# ws2812_wyswietlacz.net
KiCad netlist of a schematic drawn in EAGLE
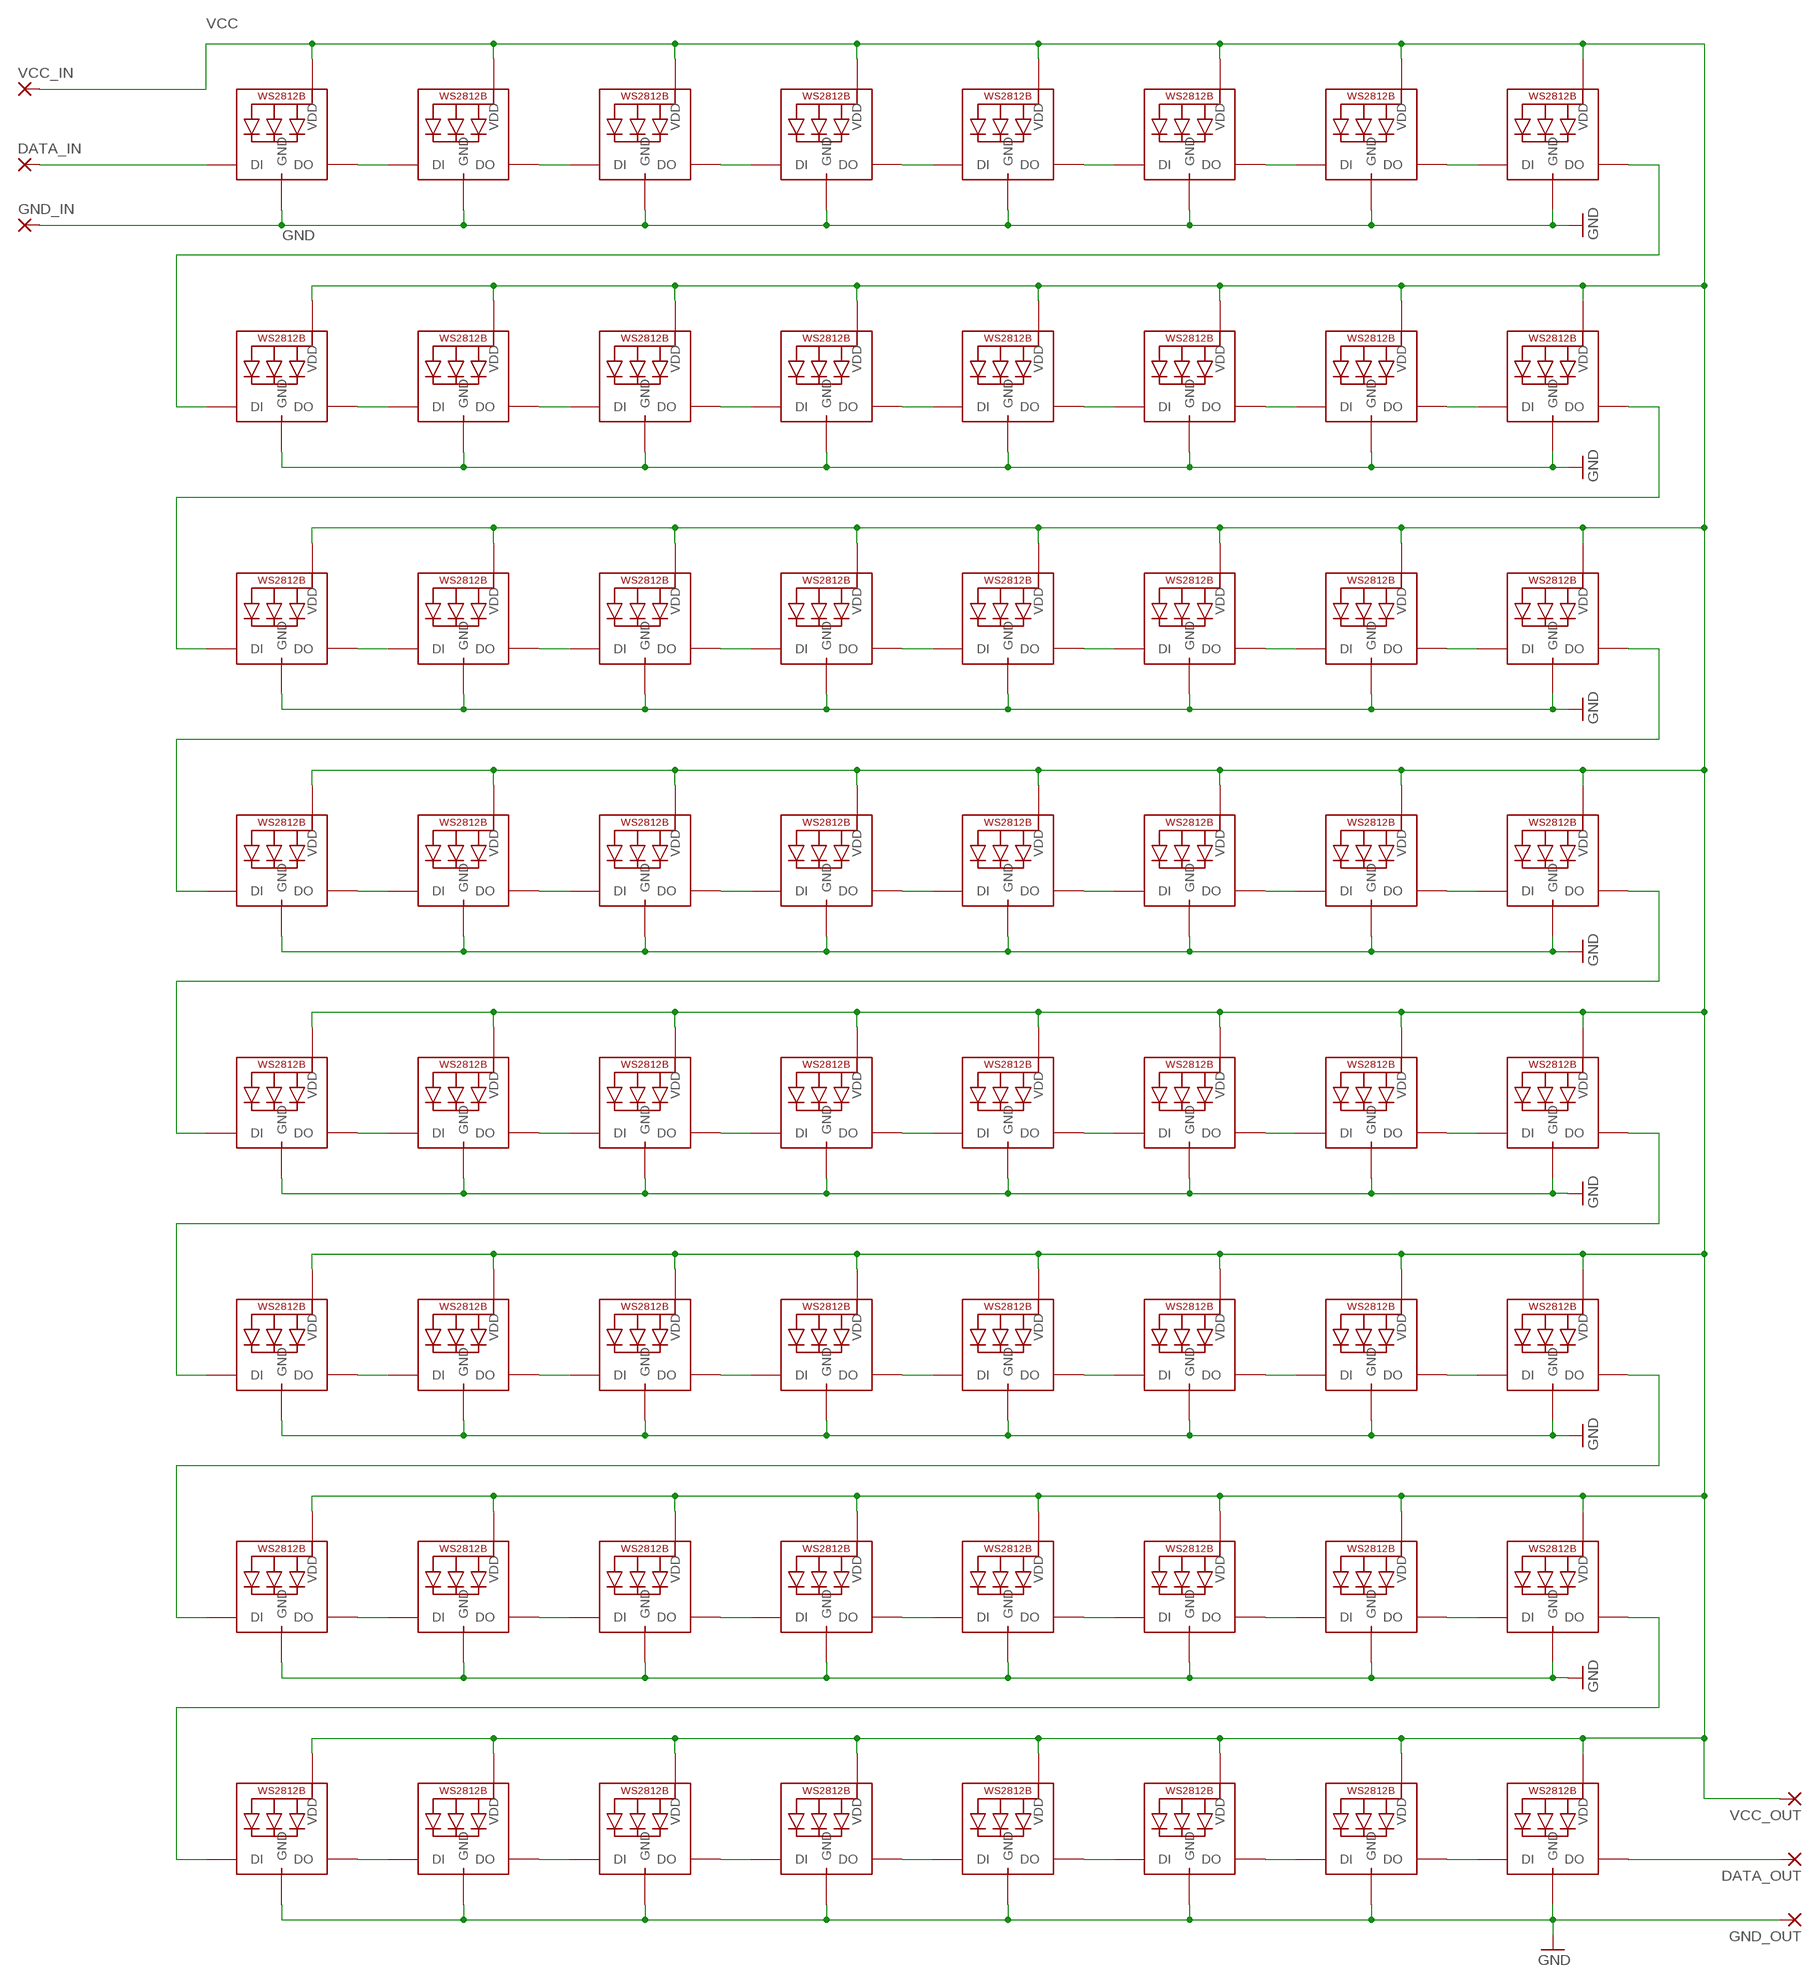
[diagram p0: schematic, sheet 1]

(export (version "E")
  (design (tool "Eeschema 10.0.6"))
  (components
    (comp (ref "DATA_IN")
      (value "2,54/1,0")
      (footprint "eagle-import:2,54_1,0")
      (libsource (lib "eagle-import") (part "2,54/1,0"))
    )
    (comp (ref "DATA_OUT")
      (value "2,54/1,0")
      (footprint "eagle-import:2,54_1,0")
      (libsource (lib "eagle-import") (part "2,54/1,0"))
    )
    (comp (ref "GND_IN")
      (value "2,54/1,0")
      (footprint "eagle-import:2,54_1,0")
      (libsource (lib "eagle-import") (part "2,54/1,0"))
    )
    (comp (ref "GND_OUT")
      (value "2,54/1,0")
      (footprint "eagle-import:2,54_1,0")
      (libsource (lib "eagle-import") (part "2,54/1,0"))
    )
    (comp (ref "LED1")
      (value "WS2812B_5050N")
      (footprint "eagle-import:WS2812B-NARROW")
      (libsource (lib "eagle-import") (part "WS2812B_5050N"))
    )
    (comp (ref "LED2")
      (value "WS2812B_5050N")
      (footprint "eagle-import:WS2812B-NARROW")
      (libsource (lib "eagle-import") (part "WS2812B_5050N"))
    )
    (comp (ref "LED3")
      (value "WS2812B_5050N")
      (footprint "eagle-import:WS2812B-NARROW")
      (libsource (lib "eagle-import") (part "WS2812B_5050N"))
    )
    (comp (ref "LED4")
      (value "WS2812B_5050N")
      (footprint "eagle-import:WS2812B-NARROW")
      (libsource (lib "eagle-import") (part "WS2812B_5050N"))
    )
    (comp (ref "LED5")
      (value "WS2812B_5050N")
      (footprint "eagle-import:WS2812B-NARROW")
      (libsource (lib "eagle-import") (part "WS2812B_5050N"))
    )
    (comp (ref "LED6")
      (value "WS2812B_5050N")
      (footprint "eagle-import:WS2812B-NARROW")
      (libsource (lib "eagle-import") (part "WS2812B_5050N"))
    )
    (comp (ref "LED7")
      (value "WS2812B_5050N")
      (footprint "eagle-import:WS2812B-NARROW")
      (libsource (lib "eagle-import") (part "WS2812B_5050N"))
    )
    (comp (ref "LED8")
      (value "WS2812B_5050N")
      (footprint "eagle-import:WS2812B-NARROW")
      (libsource (lib "eagle-import") (part "WS2812B_5050N"))
    )
    (comp (ref "LED9")
      (value "WS2812B_5050N")
      (footprint "eagle-import:WS2812B-NARROW")
      (libsource (lib "eagle-import") (part "WS2812B_5050N"))
    )
    (comp (ref "LED10")
      (value "WS2812B_5050N")
      (footprint "eagle-import:WS2812B-NARROW")
      (libsource (lib "eagle-import") (part "WS2812B_5050N"))
    )
    (comp (ref "LED11")
      (value "WS2812B_5050N")
      (footprint "eagle-import:WS2812B-NARROW")
      (libsource (lib "eagle-import") (part "WS2812B_5050N"))
    )
    (comp (ref "LED12")
      (value "WS2812B_5050N")
      (footprint "eagle-import:WS2812B-NARROW")
      (libsource (lib "eagle-import") (part "WS2812B_5050N"))
    )
    (comp (ref "LED13")
      (value "WS2812B_5050N")
      (footprint "eagle-import:WS2812B-NARROW")
      (libsource (lib "eagle-import") (part "WS2812B_5050N"))
    )
    (comp (ref "LED14")
      (value "WS2812B_5050N")
      (footprint "eagle-import:WS2812B-NARROW")
      (libsource (lib "eagle-import") (part "WS2812B_5050N"))
    )
    (comp (ref "LED15")
      (value "WS2812B_5050N")
      (footprint "eagle-import:WS2812B-NARROW")
      (libsource (lib "eagle-import") (part "WS2812B_5050N"))
    )
    (comp (ref "LED16")
      (value "WS2812B_5050N")
      (footprint "eagle-import:WS2812B-NARROW")
      (libsource (lib "eagle-import") (part "WS2812B_5050N"))
    )
    (comp (ref "LED17")
      (value "WS2812B_5050N")
      (footprint "eagle-import:WS2812B-NARROW")
      (libsource (lib "eagle-import") (part "WS2812B_5050N"))
    )
    (comp (ref "LED18")
      (value "WS2812B_5050N")
      (footprint "eagle-import:WS2812B-NARROW")
      (libsource (lib "eagle-import") (part "WS2812B_5050N"))
    )
    (comp (ref "LED19")
      (value "WS2812B_5050N")
      (footprint "eagle-import:WS2812B-NARROW")
      (libsource (lib "eagle-import") (part "WS2812B_5050N"))
    )
    (comp (ref "LED20")
      (value "WS2812B_5050N")
      (footprint "eagle-import:WS2812B-NARROW")
      (libsource (lib "eagle-import") (part "WS2812B_5050N"))
    )
    (comp (ref "LED21")
      (value "WS2812B_5050N")
      (footprint "eagle-import:WS2812B-NARROW")
      (libsource (lib "eagle-import") (part "WS2812B_5050N"))
    )
    (comp (ref "LED22")
      (value "WS2812B_5050N")
      (footprint "eagle-import:WS2812B-NARROW")
      (libsource (lib "eagle-import") (part "WS2812B_5050N"))
    )
    (comp (ref "LED23")
      (value "WS2812B_5050N")
      (footprint "eagle-import:WS2812B-NARROW")
      (libsource (lib "eagle-import") (part "WS2812B_5050N"))
    )
    (comp (ref "LED24")
      (value "WS2812B_5050N")
      (footprint "eagle-import:WS2812B-NARROW")
      (libsource (lib "eagle-import") (part "WS2812B_5050N"))
    )
    (comp (ref "LED25")
      (value "WS2812B_5050N")
      (footprint "eagle-import:WS2812B-NARROW")
      (libsource (lib "eagle-import") (part "WS2812B_5050N"))
    )
    (comp (ref "LED26")
      (value "WS2812B_5050N")
      (footprint "eagle-import:WS2812B-NARROW")
      (libsource (lib "eagle-import") (part "WS2812B_5050N"))
    )
    (comp (ref "LED27")
      (value "WS2812B_5050N")
      (footprint "eagle-import:WS2812B-NARROW")
      (libsource (lib "eagle-import") (part "WS2812B_5050N"))
    )
    (comp (ref "LED28")
      (value "WS2812B_5050N")
      (footprint "eagle-import:WS2812B-NARROW")
      (libsource (lib "eagle-import") (part "WS2812B_5050N"))
    )
    (comp (ref "LED29")
      (value "WS2812B_5050N")
      (footprint "eagle-import:WS2812B-NARROW")
      (libsource (lib "eagle-import") (part "WS2812B_5050N"))
    )
    (comp (ref "LED30")
      (value "WS2812B_5050N")
      (footprint "eagle-import:WS2812B-NARROW")
      (libsource (lib "eagle-import") (part "WS2812B_5050N"))
    )
    (comp (ref "LED31")
      (value "WS2812B_5050N")
      (footprint "eagle-import:WS2812B-NARROW")
      (libsource (lib "eagle-import") (part "WS2812B_5050N"))
    )
    (comp (ref "LED32")
      (value "WS2812B_5050N")
      (footprint "eagle-import:WS2812B-NARROW")
      (libsource (lib "eagle-import") (part "WS2812B_5050N"))
    )
    (comp (ref "LED33")
      (value "WS2812B_5050N")
      (footprint "eagle-import:WS2812B-NARROW")
      (libsource (lib "eagle-import") (part "WS2812B_5050N"))
    )
    (comp (ref "LED34")
      (value "WS2812B_5050N")
      (footprint "eagle-import:WS2812B-NARROW")
      (libsource (lib "eagle-import") (part "WS2812B_5050N"))
    )
    (comp (ref "LED35")
      (value "WS2812B_5050N")
      (footprint "eagle-import:WS2812B-NARROW")
      (libsource (lib "eagle-import") (part "WS2812B_5050N"))
    )
    (comp (ref "LED36")
      (value "WS2812B_5050N")
      (footprint "eagle-import:WS2812B-NARROW")
      (libsource (lib "eagle-import") (part "WS2812B_5050N"))
    )
    (comp (ref "LED37")
      (value "WS2812B_5050N")
      (footprint "eagle-import:WS2812B-NARROW")
      (libsource (lib "eagle-import") (part "WS2812B_5050N"))
    )
    (comp (ref "LED38")
      (value "WS2812B_5050N")
      (footprint "eagle-import:WS2812B-NARROW")
      (libsource (lib "eagle-import") (part "WS2812B_5050N"))
    )
    (comp (ref "LED39")
      (value "WS2812B_5050N")
      (footprint "eagle-import:WS2812B-NARROW")
      (libsource (lib "eagle-import") (part "WS2812B_5050N"))
    )
    (comp (ref "LED40")
      (value "WS2812B_5050N")
      (footprint "eagle-import:WS2812B-NARROW")
      (libsource (lib "eagle-import") (part "WS2812B_5050N"))
    )
    (comp (ref "LED41")
      (value "WS2812B_5050N")
      (footprint "eagle-import:WS2812B-NARROW")
      (libsource (lib "eagle-import") (part "WS2812B_5050N"))
    )
    (comp (ref "LED42")
      (value "WS2812B_5050N")
      (footprint "eagle-import:WS2812B-NARROW")
      (libsource (lib "eagle-import") (part "WS2812B_5050N"))
    )
    (comp (ref "LED43")
      (value "WS2812B_5050N")
      (footprint "eagle-import:WS2812B-NARROW")
      (libsource (lib "eagle-import") (part "WS2812B_5050N"))
    )
    (comp (ref "LED44")
      (value "WS2812B_5050N")
      (footprint "eagle-import:WS2812B-NARROW")
      (libsource (lib "eagle-import") (part "WS2812B_5050N"))
    )
    (comp (ref "LED45")
      (value "WS2812B_5050N")
      (footprint "eagle-import:WS2812B-NARROW")
      (libsource (lib "eagle-import") (part "WS2812B_5050N"))
    )
    (comp (ref "LED46")
      (value "WS2812B_5050N")
      (footprint "eagle-import:WS2812B-NARROW")
      (libsource (lib "eagle-import") (part "WS2812B_5050N"))
    )
    (comp (ref "LED47")
      (value "WS2812B_5050N")
      (footprint "eagle-import:WS2812B-NARROW")
      (libsource (lib "eagle-import") (part "WS2812B_5050N"))
    )
    (comp (ref "LED48")
      (value "WS2812B_5050N")
      (footprint "eagle-import:WS2812B-NARROW")
      (libsource (lib "eagle-import") (part "WS2812B_5050N"))
    )
    (comp (ref "LED49")
      (value "WS2812B_5050N")
      (footprint "eagle-import:WS2812B-NARROW")
      (libsource (lib "eagle-import") (part "WS2812B_5050N"))
    )
    (comp (ref "LED50")
      (value "WS2812B_5050N")
      (footprint "eagle-import:WS2812B-NARROW")
      (libsource (lib "eagle-import") (part "WS2812B_5050N"))
    )
    (comp (ref "LED51")
      (value "WS2812B_5050N")
      (footprint "eagle-import:WS2812B-NARROW")
      (libsource (lib "eagle-import") (part "WS2812B_5050N"))
    )
    (comp (ref "LED52")
      (value "WS2812B_5050N")
      (footprint "eagle-import:WS2812B-NARROW")
      (libsource (lib "eagle-import") (part "WS2812B_5050N"))
    )
    (comp (ref "LED53")
      (value "WS2812B_5050N")
      (footprint "eagle-import:WS2812B-NARROW")
      (libsource (lib "eagle-import") (part "WS2812B_5050N"))
    )
    (comp (ref "LED54")
      (value "WS2812B_5050N")
      (footprint "eagle-import:WS2812B-NARROW")
      (libsource (lib "eagle-import") (part "WS2812B_5050N"))
    )
    (comp (ref "LED55")
      (value "WS2812B_5050N")
      (footprint "eagle-import:WS2812B-NARROW")
      (libsource (lib "eagle-import") (part "WS2812B_5050N"))
    )
    (comp (ref "LED56")
      (value "WS2812B_5050N")
      (footprint "eagle-import:WS2812B-NARROW")
      (libsource (lib "eagle-import") (part "WS2812B_5050N"))
    )
    (comp (ref "LED57")
      (value "WS2812B_5050N")
      (footprint "eagle-import:WS2812B-NARROW")
      (libsource (lib "eagle-import") (part "WS2812B_5050N"))
    )
    (comp (ref "LED58")
      (value "WS2812B_5050N")
      (footprint "eagle-import:WS2812B-NARROW")
      (libsource (lib "eagle-import") (part "WS2812B_5050N"))
    )
    (comp (ref "LED59")
      (value "WS2812B_5050N")
      (footprint "eagle-import:WS2812B-NARROW")
      (libsource (lib "eagle-import") (part "WS2812B_5050N"))
    )
    (comp (ref "LED60")
      (value "WS2812B_5050N")
      (footprint "eagle-import:WS2812B-NARROW")
      (libsource (lib "eagle-import") (part "WS2812B_5050N"))
    )
    (comp (ref "LED61")
      (value "WS2812B_5050N")
      (footprint "eagle-import:WS2812B-NARROW")
      (libsource (lib "eagle-import") (part "WS2812B_5050N"))
    )
    (comp (ref "LED62")
      (value "WS2812B_5050N")
      (footprint "eagle-import:WS2812B-NARROW")
      (libsource (lib "eagle-import") (part "WS2812B_5050N"))
    )
    (comp (ref "LED63")
      (value "WS2812B_5050N")
      (footprint "eagle-import:WS2812B-NARROW")
      (libsource (lib "eagle-import") (part "WS2812B_5050N"))
    )
    (comp (ref "LED64")
      (value "WS2812B_5050N")
      (footprint "eagle-import:WS2812B-NARROW")
      (libsource (lib "eagle-import") (part "WS2812B_5050N"))
    )
    (comp (ref "VCC_IN")
      (value "2,54/1,0")
      (footprint "eagle-import:2,54_1,0")
      (libsource (lib "eagle-import") (part "2,54/1,0"))
    )
    (comp (ref "VCC_OUT")
      (value "2,54/1,0")
      (footprint "eagle-import:2,54_1,0")
      (libsource (lib "eagle-import") (part "2,54/1,0"))
    )
  )
  (nets
    (net (code "1") (name "/VCC") (class "Default")
      (node (ref "LED1") (pin "1-VDD") (pinfunction "VDD_1-VDD") (pintype "power_in"))
      (node (ref "LED10") (pin "1-VDD") (pinfunction "VDD_1-VDD") (pintype "power_in"))
      (node (ref "LED11") (pin "1-VDD") (pinfunction "VDD_1-VDD") (pintype "power_in"))
      (node (ref "LED12") (pin "1-VDD") (pinfunction "VDD_1-VDD") (pintype "power_in"))
      (node (ref "LED13") (pin "1-VDD") (pinfunction "VDD_1-VDD") (pintype "power_in"))
      (node (ref "LED14") (pin "1-VDD") (pinfunction "VDD_1-VDD") (pintype "power_in"))
      (node (ref "LED15") (pin "1-VDD") (pinfunction "VDD_1-VDD") (pintype "power_in"))
      (node (ref "LED16") (pin "1-VDD") (pinfunction "VDD_1-VDD") (pintype "power_in"))
      (node (ref "LED17") (pin "1-VDD") (pinfunction "VDD_1-VDD") (pintype "power_in"))
      (node (ref "LED18") (pin "1-VDD") (pinfunction "VDD_1-VDD") (pintype "power_in"))
      (node (ref "LED19") (pin "1-VDD") (pinfunction "VDD_1-VDD") (pintype "power_in"))
      (node (ref "LED2") (pin "1-VDD") (pinfunction "VDD_1-VDD") (pintype "power_in"))
      (node (ref "LED20") (pin "1-VDD") (pinfunction "VDD_1-VDD") (pintype "power_in"))
      (node (ref "LED21") (pin "1-VDD") (pinfunction "VDD_1-VDD") (pintype "power_in"))
      (node (ref "LED22") (pin "1-VDD") (pinfunction "VDD_1-VDD") (pintype "power_in"))
      (node (ref "LED23") (pin "1-VDD") (pinfunction "VDD_1-VDD") (pintype "power_in"))
      (node (ref "LED24") (pin "1-VDD") (pinfunction "VDD_1-VDD") (pintype "power_in"))
      (node (ref "LED25") (pin "1-VDD") (pinfunction "VDD_1-VDD") (pintype "power_in"))
      (node (ref "LED26") (pin "1-VDD") (pinfunction "VDD_1-VDD") (pintype "power_in"))
      (node (ref "LED27") (pin "1-VDD") (pinfunction "VDD_1-VDD") (pintype "power_in"))
      (node (ref "LED28") (pin "1-VDD") (pinfunction "VDD_1-VDD") (pintype "power_in"))
      (node (ref "LED29") (pin "1-VDD") (pinfunction "VDD_1-VDD") (pintype "power_in"))
      (node (ref "LED3") (pin "1-VDD") (pinfunction "VDD_1-VDD") (pintype "power_in"))
      (node (ref "LED30") (pin "1-VDD") (pinfunction "VDD_1-VDD") (pintype "power_in"))
      (node (ref "LED31") (pin "1-VDD") (pinfunction "VDD_1-VDD") (pintype "power_in"))
      (node (ref "LED32") (pin "1-VDD") (pinfunction "VDD_1-VDD") (pintype "power_in"))
      (node (ref "LED33") (pin "1-VDD") (pinfunction "VDD_1-VDD") (pintype "power_in"))
      (node (ref "LED34") (pin "1-VDD") (pinfunction "VDD_1-VDD") (pintype "power_in"))
      (node (ref "LED35") (pin "1-VDD") (pinfunction "VDD_1-VDD") (pintype "power_in"))
      (node (ref "LED36") (pin "1-VDD") (pinfunction "VDD_1-VDD") (pintype "power_in"))
      (node (ref "LED37") (pin "1-VDD") (pinfunction "VDD_1-VDD") (pintype "power_in"))
      (node (ref "LED38") (pin "1-VDD") (pinfunction "VDD_1-VDD") (pintype "power_in"))
      (node (ref "LED39") (pin "1-VDD") (pinfunction "VDD_1-VDD") (pintype "power_in"))
      (node (ref "LED4") (pin "1-VDD") (pinfunction "VDD_1-VDD") (pintype "power_in"))
      (node (ref "LED40") (pin "1-VDD") (pinfunction "VDD_1-VDD") (pintype "power_in"))
      (node (ref "LED41") (pin "1-VDD") (pinfunction "VDD_1-VDD") (pintype "power_in"))
      (node (ref "LED42") (pin "1-VDD") (pinfunction "VDD_1-VDD") (pintype "power_in"))
      (node (ref "LED43") (pin "1-VDD") (pinfunction "VDD_1-VDD") (pintype "power_in"))
      (node (ref "LED44") (pin "1-VDD") (pinfunction "VDD_1-VDD") (pintype "power_in"))
      (node (ref "LED45") (pin "1-VDD") (pinfunction "VDD_1-VDD") (pintype "power_in"))
      (node (ref "LED46") (pin "1-VDD") (pinfunction "VDD_1-VDD") (pintype "power_in"))
      (node (ref "LED47") (pin "1-VDD") (pinfunction "VDD_1-VDD") (pintype "power_in"))
      (node (ref "LED48") (pin "1-VDD") (pinfunction "VDD_1-VDD") (pintype "power_in"))
      (node (ref "LED49") (pin "1-VDD") (pinfunction "VDD_1-VDD") (pintype "power_in"))
      (node (ref "LED5") (pin "1-VDD") (pinfunction "VDD_1-VDD") (pintype "power_in"))
      (node (ref "LED50") (pin "1-VDD") (pinfunction "VDD_1-VDD") (pintype "power_in"))
      (node (ref "LED51") (pin "1-VDD") (pinfunction "VDD_1-VDD") (pintype "power_in"))
      (node (ref "LED52") (pin "1-VDD") (pinfunction "VDD_1-VDD") (pintype "power_in"))
      (node (ref "LED53") (pin "1-VDD") (pinfunction "VDD_1-VDD") (pintype "power_in"))
      (node (ref "LED54") (pin "1-VDD") (pinfunction "VDD_1-VDD") (pintype "power_in"))
      (node (ref "LED55") (pin "1-VDD") (pinfunction "VDD_1-VDD") (pintype "power_in"))
      (node (ref "LED56") (pin "1-VDD") (pinfunction "VDD_1-VDD") (pintype "power_in"))
      (node (ref "LED57") (pin "1-VDD") (pinfunction "VDD_1-VDD") (pintype "power_in"))
      (node (ref "LED58") (pin "1-VDD") (pinfunction "VDD_1-VDD") (pintype "power_in"))
      (node (ref "LED59") (pin "1-VDD") (pinfunction "VDD_1-VDD") (pintype "power_in"))
      (node (ref "LED6") (pin "1-VDD") (pinfunction "VDD_1-VDD") (pintype "power_in"))
      (node (ref "LED60") (pin "1-VDD") (pinfunction "VDD_1-VDD") (pintype "power_in"))
      (node (ref "LED61") (pin "1-VDD") (pinfunction "VDD_1-VDD") (pintype "power_in"))
      (node (ref "LED62") (pin "1-VDD") (pinfunction "VDD_1-VDD") (pintype "power_in"))
      (node (ref "LED63") (pin "1-VDD") (pinfunction "VDD_1-VDD") (pintype "power_in"))
      (node (ref "LED64") (pin "1-VDD") (pinfunction "VDD_1-VDD") (pintype "power_in"))
      (node (ref "LED7") (pin "1-VDD") (pinfunction "VDD_1-VDD") (pintype "power_in"))
      (node (ref "LED8") (pin "1-VDD") (pinfunction "VDD_1-VDD") (pintype "power_in"))
      (node (ref "LED9") (pin "1-VDD") (pinfunction "VDD_1-VDD") (pintype "power_in"))
      (node (ref "VCC_IN") (pin "1") (pinfunction "P_1") (pintype "passive"))
      (node (ref "VCC_OUT") (pin "1") (pinfunction "P_1") (pintype "passive"))
    )
    (net (code "2") (name "GND") (class "Default")
      (node (ref "GND_IN") (pin "1") (pinfunction "P_1") (pintype "passive"))
      (node (ref "GND_OUT") (pin "1") (pinfunction "P_1") (pintype "passive"))
      (node (ref "LED1") (pin "3-GND") (pinfunction "GND_3-GND") (pintype "power_in"))
      (node (ref "LED10") (pin "3-GND") (pinfunction "GND_3-GND") (pintype "power_in"))
      (node (ref "LED11") (pin "3-GND") (pinfunction "GND_3-GND") (pintype "power_in"))
      (node (ref "LED12") (pin "3-GND") (pinfunction "GND_3-GND") (pintype "power_in"))
      (node (ref "LED13") (pin "3-GND") (pinfunction "GND_3-GND") (pintype "power_in"))
      (node (ref "LED14") (pin "3-GND") (pinfunction "GND_3-GND") (pintype "power_in"))
      (node (ref "LED15") (pin "3-GND") (pinfunction "GND_3-GND") (pintype "power_in"))
      (node (ref "LED16") (pin "3-GND") (pinfunction "GND_3-GND") (pintype "power_in"))
      (node (ref "LED17") (pin "3-GND") (pinfunction "GND_3-GND") (pintype "power_in"))
      (node (ref "LED18") (pin "3-GND") (pinfunction "GND_3-GND") (pintype "power_in"))
      (node (ref "LED19") (pin "3-GND") (pinfunction "GND_3-GND") (pintype "power_in"))
      (node (ref "LED2") (pin "3-GND") (pinfunction "GND_3-GND") (pintype "power_in"))
      (node (ref "LED20") (pin "3-GND") (pinfunction "GND_3-GND") (pintype "power_in"))
      (node (ref "LED21") (pin "3-GND") (pinfunction "GND_3-GND") (pintype "power_in"))
      (node (ref "LED22") (pin "3-GND") (pinfunction "GND_3-GND") (pintype "power_in"))
      (node (ref "LED23") (pin "3-GND") (pinfunction "GND_3-GND") (pintype "power_in"))
      (node (ref "LED24") (pin "3-GND") (pinfunction "GND_3-GND") (pintype "power_in"))
      (node (ref "LED25") (pin "3-GND") (pinfunction "GND_3-GND") (pintype "power_in"))
      (node (ref "LED26") (pin "3-GND") (pinfunction "GND_3-GND") (pintype "power_in"))
      (node (ref "LED27") (pin "3-GND") (pinfunction "GND_3-GND") (pintype "power_in"))
      (node (ref "LED28") (pin "3-GND") (pinfunction "GND_3-GND") (pintype "power_in"))
      (node (ref "LED29") (pin "3-GND") (pinfunction "GND_3-GND") (pintype "power_in"))
      (node (ref "LED3") (pin "3-GND") (pinfunction "GND_3-GND") (pintype "power_in"))
      (node (ref "LED30") (pin "3-GND") (pinfunction "GND_3-GND") (pintype "power_in"))
      (node (ref "LED31") (pin "3-GND") (pinfunction "GND_3-GND") (pintype "power_in"))
      (node (ref "LED32") (pin "3-GND") (pinfunction "GND_3-GND") (pintype "power_in"))
      (node (ref "LED33") (pin "3-GND") (pinfunction "GND_3-GND") (pintype "power_in"))
      (node (ref "LED34") (pin "3-GND") (pinfunction "GND_3-GND") (pintype "power_in"))
      (node (ref "LED35") (pin "3-GND") (pinfunction "GND_3-GND") (pintype "power_in"))
      (node (ref "LED36") (pin "3-GND") (pinfunction "GND_3-GND") (pintype "power_in"))
      (node (ref "LED37") (pin "3-GND") (pinfunction "GND_3-GND") (pintype "power_in"))
      (node (ref "LED38") (pin "3-GND") (pinfunction "GND_3-GND") (pintype "power_in"))
      (node (ref "LED39") (pin "3-GND") (pinfunction "GND_3-GND") (pintype "power_in"))
      (node (ref "LED4") (pin "3-GND") (pinfunction "GND_3-GND") (pintype "power_in"))
      (node (ref "LED40") (pin "3-GND") (pinfunction "GND_3-GND") (pintype "power_in"))
      (node (ref "LED41") (pin "3-GND") (pinfunction "GND_3-GND") (pintype "power_in"))
      (node (ref "LED42") (pin "3-GND") (pinfunction "GND_3-GND") (pintype "power_in"))
      (node (ref "LED43") (pin "3-GND") (pinfunction "GND_3-GND") (pintype "power_in"))
      (node (ref "LED44") (pin "3-GND") (pinfunction "GND_3-GND") (pintype "power_in"))
      (node (ref "LED45") (pin "3-GND") (pinfunction "GND_3-GND") (pintype "power_in"))
      (node (ref "LED46") (pin "3-GND") (pinfunction "GND_3-GND") (pintype "power_in"))
      (node (ref "LED47") (pin "3-GND") (pinfunction "GND_3-GND") (pintype "power_in"))
      (node (ref "LED48") (pin "3-GND") (pinfunction "GND_3-GND") (pintype "power_in"))
      (node (ref "LED49") (pin "3-GND") (pinfunction "GND_3-GND") (pintype "power_in"))
      (node (ref "LED5") (pin "3-GND") (pinfunction "GND_3-GND") (pintype "power_in"))
      (node (ref "LED50") (pin "3-GND") (pinfunction "GND_3-GND") (pintype "power_in"))
      (node (ref "LED51") (pin "3-GND") (pinfunction "GND_3-GND") (pintype "power_in"))
      (node (ref "LED52") (pin "3-GND") (pinfunction "GND_3-GND") (pintype "power_in"))
      (node (ref "LED53") (pin "3-GND") (pinfunction "GND_3-GND") (pintype "power_in"))
      (node (ref "LED54") (pin "3-GND") (pinfunction "GND_3-GND") (pintype "power_in"))
      (node (ref "LED55") (pin "3-GND") (pinfunction "GND_3-GND") (pintype "power_in"))
      (node (ref "LED56") (pin "3-GND") (pinfunction "GND_3-GND") (pintype "power_in"))
      (node (ref "LED57") (pin "3-GND") (pinfunction "GND_3-GND") (pintype "power_in"))
      (node (ref "LED58") (pin "3-GND") (pinfunction "GND_3-GND") (pintype "power_in"))
      (node (ref "LED59") (pin "3-GND") (pinfunction "GND_3-GND") (pintype "power_in"))
      (node (ref "LED6") (pin "3-GND") (pinfunction "GND_3-GND") (pintype "power_in"))
      (node (ref "LED60") (pin "3-GND") (pinfunction "GND_3-GND") (pintype "power_in"))
      (node (ref "LED61") (pin "3-GND") (pinfunction "GND_3-GND") (pintype "power_in"))
      (node (ref "LED62") (pin "3-GND") (pinfunction "GND_3-GND") (pintype "power_in"))
      (node (ref "LED63") (pin "3-GND") (pinfunction "GND_3-GND") (pintype "power_in"))
      (node (ref "LED64") (pin "3-GND") (pinfunction "GND_3-GND") (pintype "power_in"))
      (node (ref "LED7") (pin "3-GND") (pinfunction "GND_3-GND") (pintype "power_in"))
      (node (ref "LED8") (pin "3-GND") (pinfunction "GND_3-GND") (pintype "power_in"))
      (node (ref "LED9") (pin "3-GND") (pinfunction "GND_3-GND") (pintype "power_in"))
    )
    (net (code "3") (name "Net-(DATA_IN-P)") (class "Default")
      (node (ref "DATA_IN") (pin "1") (pinfunction "P_1") (pintype "passive"))
      (node (ref "LED1") (pin "4-DIN") (pinfunction "DI_4-DIN") (pintype "input"))
    )
    (net (code "4") (name "Net-(DATA_OUT-P)") (class "Default")
      (node (ref "DATA_OUT") (pin "1") (pinfunction "P_1") (pintype "passive"))
      (node (ref "LED64") (pin "2-DOUT") (pinfunction "DO_2-DOUT") (pintype "output"))
    )
    (net (code "5") (name "Net-(LED1-DO)") (class "Default")
      (node (ref "LED1") (pin "2-DOUT") (pinfunction "DO_2-DOUT") (pintype "output"))
      (node (ref "LED2") (pin "4-DIN") (pinfunction "DI_4-DIN") (pintype "input"))
    )
    (net (code "6") (name "Net-(LED2-DO)") (class "Default")
      (node (ref "LED2") (pin "2-DOUT") (pinfunction "DO_2-DOUT") (pintype "output"))
      (node (ref "LED3") (pin "4-DIN") (pinfunction "DI_4-DIN") (pintype "input"))
    )
    (net (code "7") (name "Net-(LED3-DO)") (class "Default")
      (node (ref "LED3") (pin "2-DOUT") (pinfunction "DO_2-DOUT") (pintype "output"))
      (node (ref "LED4") (pin "4-DIN") (pinfunction "DI_4-DIN") (pintype "input"))
    )
    (net (code "8") (name "Net-(LED4-DO)") (class "Default")
      (node (ref "LED4") (pin "2-DOUT") (pinfunction "DO_2-DOUT") (pintype "output"))
      (node (ref "LED5") (pin "4-DIN") (pinfunction "DI_4-DIN") (pintype "input"))
    )
    (net (code "9") (name "Net-(LED5-DO)") (class "Default")
      (node (ref "LED5") (pin "2-DOUT") (pinfunction "DO_2-DOUT") (pintype "output"))
      (node (ref "LED6") (pin "4-DIN") (pinfunction "DI_4-DIN") (pintype "input"))
    )
    (net (code "10") (name "Net-(LED6-DO)") (class "Default")
      (node (ref "LED6") (pin "2-DOUT") (pinfunction "DO_2-DOUT") (pintype "output"))
      (node (ref "LED7") (pin "4-DIN") (pinfunction "DI_4-DIN") (pintype "input"))
    )
    (net (code "11") (name "Net-(LED7-DO)") (class "Default")
      (node (ref "LED7") (pin "2-DOUT") (pinfunction "DO_2-DOUT") (pintype "output"))
      (node (ref "LED8") (pin "4-DIN") (pinfunction "DI_4-DIN") (pintype "input"))
    )
    (net (code "12") (name "Net-(LED8-DO)") (class "Default")
      (node (ref "LED8") (pin "2-DOUT") (pinfunction "DO_2-DOUT") (pintype "output"))
      (node (ref "LED9") (pin "4-DIN") (pinfunction "DI_4-DIN") (pintype "input"))
    )
    (net (code "13") (name "Net-(LED10-DI)") (class "Default")
      (node (ref "LED10") (pin "4-DIN") (pinfunction "DI_4-DIN") (pintype "input"))
      (node (ref "LED9") (pin "2-DOUT") (pinfunction "DO_2-DOUT") (pintype "output"))
    )
    (net (code "14") (name "Net-(LED10-DO)") (class "Default")
      (node (ref "LED10") (pin "2-DOUT") (pinfunction "DO_2-DOUT") (pintype "output"))
      (node (ref "LED11") (pin "4-DIN") (pinfunction "DI_4-DIN") (pintype "input"))
    )
    (net (code "15") (name "Net-(LED11-DO)") (class "Default")
      (node (ref "LED11") (pin "2-DOUT") (pinfunction "DO_2-DOUT") (pintype "output"))
      (node (ref "LED12") (pin "4-DIN") (pinfunction "DI_4-DIN") (pintype "input"))
    )
    (net (code "16") (name "Net-(LED12-DO)") (class "Default")
      (node (ref "LED12") (pin "2-DOUT") (pinfunction "DO_2-DOUT") (pintype "output"))
      (node (ref "LED13") (pin "4-DIN") (pinfunction "DI_4-DIN") (pintype "input"))
    )
    (net (code "17") (name "Net-(LED13-DO)") (class "Default")
      (node (ref "LED13") (pin "2-DOUT") (pinfunction "DO_2-DOUT") (pintype "output"))
      (node (ref "LED14") (pin "4-DIN") (pinfunction "DI_4-DIN") (pintype "input"))
    )
    (net (code "18") (name "Net-(LED14-DO)") (class "Default")
      (node (ref "LED14") (pin "2-DOUT") (pinfunction "DO_2-DOUT") (pintype "output"))
      (node (ref "LED15") (pin "4-DIN") (pinfunction "DI_4-DIN") (pintype "input"))
    )
    (net (code "19") (name "Net-(LED15-DO)") (class "Default")
      (node (ref "LED15") (pin "2-DOUT") (pinfunction "DO_2-DOUT") (pintype "output"))
      (node (ref "LED16") (pin "4-DIN") (pinfunction "DI_4-DIN") (pintype "input"))
    )
    (net (code "20") (name "Net-(LED16-DO)") (class "Default")
      (node (ref "LED16") (pin "2-DOUT") (pinfunction "DO_2-DOUT") (pintype "output"))
      (node (ref "LED17") (pin "4-DIN") (pinfunction "DI_4-DIN") (pintype "input"))
    )
    (net (code "21") (name "Net-(LED17-DO)") (class "Default")
      (node (ref "LED17") (pin "2-DOUT") (pinfunction "DO_2-DOUT") (pintype "output"))
      (node (ref "LED18") (pin "4-DIN") (pinfunction "DI_4-DIN") (pintype "input"))
    )
    (net (code "22") (name "Net-(LED18-DO)") (class "Default")
      (node (ref "LED18") (pin "2-DOUT") (pinfunction "DO_2-DOUT") (pintype "output"))
      (node (ref "LED19") (pin "4-DIN") (pinfunction "DI_4-DIN") (pintype "input"))
    )
    (net (code "23") (name "Net-(LED19-DO)") (class "Default")
      (node (ref "LED19") (pin "2-DOUT") (pinfunction "DO_2-DOUT") (pintype "output"))
      (node (ref "LED20") (pin "4-DIN") (pinfunction "DI_4-DIN") (pintype "input"))
    )
    (net (code "24") (name "Net-(LED20-DO)") (class "Default")
      (node (ref "LED20") (pin "2-DOUT") (pinfunction "DO_2-DOUT") (pintype "output"))
      (node (ref "LED21") (pin "4-DIN") (pinfunction "DI_4-DIN") (pintype "input"))
    )
    (net (code "25") (name "Net-(LED21-DO)") (class "Default")
      (node (ref "LED21") (pin "2-DOUT") (pinfunction "DO_2-DOUT") (pintype "output"))
      (node (ref "LED22") (pin "4-DIN") (pinfunction "DI_4-DIN") (pintype "input"))
    )
    (net (code "26") (name "Net-(LED22-DO)") (class "Default")
      (node (ref "LED22") (pin "2-DOUT") (pinfunction "DO_2-DOUT") (pintype "output"))
      (node (ref "LED23") (pin "4-DIN") (pinfunction "DI_4-DIN") (pintype "input"))
    )
    (net (code "27") (name "Net-(LED23-DO)") (class "Default")
      (node (ref "LED23") (pin "2-DOUT") (pinfunction "DO_2-DOUT") (pintype "output"))
      (node (ref "LED24") (pin "4-DIN") (pinfunction "DI_4-DIN") (pintype "input"))
    )
    (net (code "28") (name "Net-(LED24-DO)") (class "Default")
      (node (ref "LED24") (pin "2-DOUT") (pinfunction "DO_2-DOUT") (pintype "output"))
      (node (ref "LED25") (pin "4-DIN") (pinfunction "DI_4-DIN") (pintype "input"))
    )
    (net (code "29") (name "Net-(LED25-DO)") (class "Default")
      (node (ref "LED25") (pin "2-DOUT") (pinfunction "DO_2-DOUT") (pintype "output"))
      (node (ref "LED26") (pin "4-DIN") (pinfunction "DI_4-DIN") (pintype "input"))
    )
    (net (code "30") (name "Net-(LED26-DO)") (class "Default")
      (node (ref "LED26") (pin "2-DOUT") (pinfunction "DO_2-DOUT") (pintype "output"))
      (node (ref "LED27") (pin "4-DIN") (pinfunction "DI_4-DIN") (pintype "input"))
    )
    (net (code "31") (name "Net-(LED27-DO)") (class "Default")
      (node (ref "LED27") (pin "2-DOUT") (pinfunction "DO_2-DOUT") (pintype "output"))
      (node (ref "LED28") (pin "4-DIN") (pinfunction "DI_4-DIN") (pintype "input"))
    )
    (net (code "32") (name "Net-(LED28-DO)") (class "Default")
      (node (ref "LED28") (pin "2-DOUT") (pinfunction "DO_2-DOUT") (pintype "output"))
      (node (ref "LED29") (pin "4-DIN") (pinfunction "DI_4-DIN") (pintype "input"))
    )
    (net (code "33") (name "Net-(LED29-DO)") (class "Default")
      (node (ref "LED29") (pin "2-DOUT") (pinfunction "DO_2-DOUT") (pintype "output"))
      (node (ref "LED30") (pin "4-DIN") (pinfunction "DI_4-DIN") (pintype "input"))
    )
    (net (code "34") (name "Net-(LED30-DO)") (class "Default")
      (node (ref "LED30") (pin "2-DOUT") (pinfunction "DO_2-DOUT") (pintype "output"))
      (node (ref "LED31") (pin "4-DIN") (pinfunction "DI_4-DIN") (pintype "input"))
    )
    (net (code "35") (name "Net-(LED31-DO)") (class "Default")
      (node (ref "LED31") (pin "2-DOUT") (pinfunction "DO_2-DOUT") (pintype "output"))
      (node (ref "LED32") (pin "4-DIN") (pinfunction "DI_4-DIN") (pintype "input"))
    )
    (net (code "36") (name "Net-(LED32-DO)") (class "Default")
      (node (ref "LED32") (pin "2-DOUT") (pinfunction "DO_2-DOUT") (pintype "output"))
      (node (ref "LED33") (pin "4-DIN") (pinfunction "DI_4-DIN") (pintype "input"))
    )
    (net (code "37") (name "Net-(LED33-DO)") (class "Default")
      (node (ref "LED33") (pin "2-DOUT") (pinfunction "DO_2-DOUT") (pintype "output"))
      (node (ref "LED34") (pin "4-DIN") (pinfunction "DI_4-DIN") (pintype "input"))
    )
    (net (code "38") (name "Net-(LED34-DO)") (class "Default")
      (node (ref "LED34") (pin "2-DOUT") (pinfunction "DO_2-DOUT") (pintype "output"))
      (node (ref "LED35") (pin "4-DIN") (pinfunction "DI_4-DIN") (pintype "input"))
    )
    (net (code "39") (name "Net-(LED35-DO)") (class "Default")
      (node (ref "LED35") (pin "2-DOUT") (pinfunction "DO_2-DOUT") (pintype "output"))
      (node (ref "LED36") (pin "4-DIN") (pinfunction "DI_4-DIN") (pintype "input"))
    )
    (net (code "40") (name "Net-(LED36-DO)") (class "Default")
      (node (ref "LED36") (pin "2-DOUT") (pinfunction "DO_2-DOUT") (pintype "output"))
      (node (ref "LED37") (pin "4-DIN") (pinfunction "DI_4-DIN") (pintype "input"))
    )
    (net (code "41") (name "Net-(LED37-DO)") (class "Default")
      (node (ref "LED37") (pin "2-DOUT") (pinfunction "DO_2-DOUT") (pintype "output"))
      (node (ref "LED38") (pin "4-DIN") (pinfunction "DI_4-DIN") (pintype "input"))
    )
    (net (code "42") (name "Net-(LED38-DO)") (class "Default")
      (node (ref "LED38") (pin "2-DOUT") (pinfunction "DO_2-DOUT") (pintype "output"))
      (node (ref "LED39") (pin "4-DIN") (pinfunction "DI_4-DIN") (pintype "input"))
    )
    (net (code "43") (name "Net-(LED39-DO)") (class "Default")
      (node (ref "LED39") (pin "2-DOUT") (pinfunction "DO_2-DOUT") (pintype "output"))
      (node (ref "LED40") (pin "4-DIN") (pinfunction "DI_4-DIN") (pintype "input"))
    )
    (net (code "44") (name "Net-(LED40-DO)") (class "Default")
      (node (ref "LED40") (pin "2-DOUT") (pinfunction "DO_2-DOUT") (pintype "output"))
      (node (ref "LED41") (pin "4-DIN") (pinfunction "DI_4-DIN") (pintype "input"))
    )
    (net (code "45") (name "Net-(LED41-DO)") (class "Default")
      (node (ref "LED41") (pin "2-DOUT") (pinfunction "DO_2-DOUT") (pintype "output"))
      (node (ref "LED42") (pin "4-DIN") (pinfunction "DI_4-DIN") (pintype "input"))
    )
    (net (code "46") (name "Net-(LED42-DO)") (class "Default")
      (node (ref "LED42") (pin "2-DOUT") (pinfunction "DO_2-DOUT") (pintype "output"))
      (node (ref "LED43") (pin "4-DIN") (pinfunction "DI_4-DIN") (pintype "input"))
    )
    (net (code "47") (name "Net-(LED43-DO)") (class "Default")
      (node (ref "LED43") (pin "2-DOUT") (pinfunction "DO_2-DOUT") (pintype "output"))
      (node (ref "LED44") (pin "4-DIN") (pinfunction "DI_4-DIN") (pintype "input"))
    )
    (net (code "48") (name "Net-(LED44-DO)") (class "Default")
      (node (ref "LED44") (pin "2-DOUT") (pinfunction "DO_2-DOUT") (pintype "output"))
      (node (ref "LED45") (pin "4-DIN") (pinfunction "DI_4-DIN") (pintype "input"))
    )
    (net (code "49") (name "Net-(LED45-DO)") (class "Default")
      (node (ref "LED45") (pin "2-DOUT") (pinfunction "DO_2-DOUT") (pintype "output"))
      (node (ref "LED46") (pin "4-DIN") (pinfunction "DI_4-DIN") (pintype "input"))
    )
    (net (code "50") (name "Net-(LED46-DO)") (class "Default")
      (node (ref "LED46") (pin "2-DOUT") (pinfunction "DO_2-DOUT") (pintype "output"))
      (node (ref "LED47") (pin "4-DIN") (pinfunction "DI_4-DIN") (pintype "input"))
    )
    (net (code "51") (name "Net-(LED47-DO)") (class "Default")
      (node (ref "LED47") (pin "2-DOUT") (pinfunction "DO_2-DOUT") (pintype "output"))
      (node (ref "LED48") (pin "4-DIN") (pinfunction "DI_4-DIN") (pintype "input"))
    )
    (net (code "52") (name "Net-(LED48-DO)") (class "Default")
      (node (ref "LED48") (pin "2-DOUT") (pinfunction "DO_2-DOUT") (pintype "output"))
      (node (ref "LED49") (pin "4-DIN") (pinfunction "DI_4-DIN") (pintype "input"))
    )
    (net (code "53") (name "Net-(LED49-DO)") (class "Default")
      (node (ref "LED49") (pin "2-DOUT") (pinfunction "DO_2-DOUT") (pintype "output"))
      (node (ref "LED50") (pin "4-DIN") (pinfunction "DI_4-DIN") (pintype "input"))
    )
    (net (code "54") (name "Net-(LED50-DO)") (class "Default")
      (node (ref "LED50") (pin "2-DOUT") (pinfunction "DO_2-DOUT") (pintype "output"))
      (node (ref "LED51") (pin "4-DIN") (pinfunction "DI_4-DIN") (pintype "input"))
    )
    (net (code "55") (name "Net-(LED51-DO)") (class "Default")
      (node (ref "LED51") (pin "2-DOUT") (pinfunction "DO_2-DOUT") (pintype "output"))
      (node (ref "LED52") (pin "4-DIN") (pinfunction "DI_4-DIN") (pintype "input"))
    )
    (net (code "56") (name "Net-(LED52-DO)") (class "Default")
      (node (ref "LED52") (pin "2-DOUT") (pinfunction "DO_2-DOUT") (pintype "output"))
      (node (ref "LED53") (pin "4-DIN") (pinfunction "DI_4-DIN") (pintype "input"))
    )
    (net (code "57") (name "Net-(LED53-DO)") (class "Default")
      (node (ref "LED53") (pin "2-DOUT") (pinfunction "DO_2-DOUT") (pintype "output"))
      (node (ref "LED54") (pin "4-DIN") (pinfunction "DI_4-DIN") (pintype "input"))
    )
    (net (code "58") (name "Net-(LED54-DO)") (class "Default")
      (node (ref "LED54") (pin "2-DOUT") (pinfunction "DO_2-DOUT") (pintype "output"))
      (node (ref "LED55") (pin "4-DIN") (pinfunction "DI_4-DIN") (pintype "input"))
    )
    (net (code "59") (name "Net-(LED55-DO)") (class "Default")
      (node (ref "LED55") (pin "2-DOUT") (pinfunction "DO_2-DOUT") (pintype "output"))
      (node (ref "LED56") (pin "4-DIN") (pinfunction "DI_4-DIN") (pintype "input"))
    )
    (net (code "60") (name "Net-(LED56-DO)") (class "Default")
      (node (ref "LED56") (pin "2-DOUT") (pinfunction "DO_2-DOUT") (pintype "output"))
      (node (ref "LED57") (pin "4-DIN") (pinfunction "DI_4-DIN") (pintype "input"))
    )
    (net (code "61") (name "Net-(LED57-DO)") (class "Default")
      (node (ref "LED57") (pin "2-DOUT") (pinfunction "DO_2-DOUT") (pintype "output"))
      (node (ref "LED58") (pin "4-DIN") (pinfunction "DI_4-DIN") (pintype "input"))
    )
    (net (code "62") (name "Net-(LED58-DO)") (class "Default")
      (node (ref "LED58") (pin "2-DOUT") (pinfunction "DO_2-DOUT") (pintype "output"))
      (node (ref "LED59") (pin "4-DIN") (pinfunction "DI_4-DIN") (pintype "input"))
    )
    (net (code "63") (name "Net-(LED59-DO)") (class "Default")
      (node (ref "LED59") (pin "2-DOUT") (pinfunction "DO_2-DOUT") (pintype "output"))
      (node (ref "LED60") (pin "4-DIN") (pinfunction "DI_4-DIN") (pintype "input"))
    )
    (net (code "64") (name "Net-(LED60-DO)") (class "Default")
      (node (ref "LED60") (pin "2-DOUT") (pinfunction "DO_2-DOUT") (pintype "output"))
      (node (ref "LED61") (pin "4-DIN") (pinfunction "DI_4-DIN") (pintype "input"))
    )
    (net (code "65") (name "Net-(LED61-DO)") (class "Default")
      (node (ref "LED61") (pin "2-DOUT") (pinfunction "DO_2-DOUT") (pintype "output"))
      (node (ref "LED62") (pin "4-DIN") (pinfunction "DI_4-DIN") (pintype "input"))
    )
    (net (code "66") (name "Net-(LED62-DO)") (class "Default")
      (node (ref "LED62") (pin "2-DOUT") (pinfunction "DO_2-DOUT") (pintype "output"))
      (node (ref "LED63") (pin "4-DIN") (pinfunction "DI_4-DIN") (pintype "input"))
    )
    (net (code "67") (name "Net-(LED63-DO)") (class "Default")
      (node (ref "LED63") (pin "2-DOUT") (pinfunction "DO_2-DOUT") (pintype "output"))
      (node (ref "LED64") (pin "4-DIN") (pinfunction "DI_4-DIN") (pintype "input"))
    )
  )
)
